# Power_Switch.net
KiCad netlist of a schematic drawn in Altium Designer
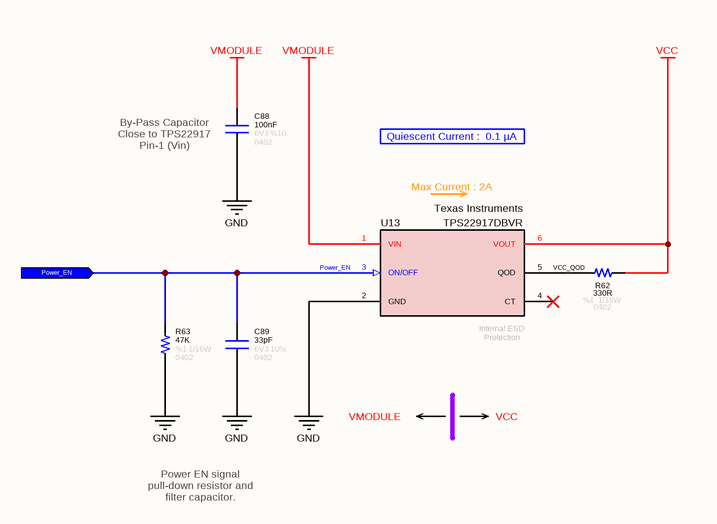
[diagram p0: Power Switch.SchDoc]

(export (version "E")
  (design (tool "Eeschema 10.0.6"))
  (components
    (comp (ref "C88")
      (value "100nF")
      (footprint "CAPACITOR_0402")
      (description "Capacitor - 100nF [0402-6V3] (Ceramic)")
      (fields
        (field (name "MANUFACTURER PART NUMBER") "04026D104KAT4A")
        (field (name "TOLERANCE") "%10")
        (field (name "VOLTAGE") "6V3")
        (field (name "CASE") "0402")
        (field (name "Comment") "Capacitor - 100nF [0402] (Ceramic)")
      )
      (libsource (lib "P101DA_Library") (part "Capacitor - 100nF [0402-6V3]"))
    )
    (comp (ref "C89")
      (value "33pF")
      (footprint "CAPACITOR_0402")
      (description "Capacitor - 33pF [0402] (Ceramic)")
      (fields
        (field (name "MANUFACTURER PART NUMBER") "C0402C330J9RACAUTO")
        (field (name "TOLERANCE") "10%")
        (field (name "CASE") "0402")
        (field (name "VOLTAGE") "6V3")
      )
      (libsource (lib "P101DA_Library") (part "Capacitor - 33pF [0402-6V3]"))
    )
    (comp (ref "R62")
      (value "330R")
      (footprint "RESISTOR_0402")
      (description "Thick Film Resistors - SMD 1/16 W 330 Ohm 1%")
      (fields
        (field (name "MANUFACTURER PART NUMBER") "CRCW0402330RFKED")
        (field (name "CASE") "0402")
        (field (name "TOLERANCE") "%1")
        (field (name "POWER") "1/16W")
        (field (name "Comment") "330R - 0402 - %1 - 1/16W")
      )
      (libsource (lib "P101DA_Library") (part "Resistor - 330R [0402]"))
    )
    (comp (ref "R63")
      (value "47K")
      (footprint "RESISTOR_0402")
      (description "Thick Film Resistors - SMD 1/16 W 47 KOhm 1%")
      (fields
        (field (name "MANUFACTURER PART NUMBER") "CRCW040247K0FKED")
        (field (name "TOLERANCE") "%1")
        (field (name "CASE") "0402")
        (field (name "POWER") "1/16W")
        (field (name "Comment") "47K - 0402 - %1 - 1/16W")
      )
      (libsource (lib "P101DA_Library") (part "Resistor - 47K [0402]"))
    )
    (comp (ref "U13")
      (value "Power Switch")
      (footprint "SOT-23-6")
      (description "Power Switch MosFet")
      (fields
        (field (name "MANUFACTURER PART NUMBER") "TPS22917DBVR")
        (field (name "MANUFACTURER NAME") "Texas Instruments")
      )
      (libsource (lib "P101DA_Library") (part "IC - TPS22917"))
    )
  )
  (nets
    (net (code "1") (name "/Power_EN") (class "Default")
      (node (ref "C89") (pin "2") (pinfunction "2_2") (pintype "passive"))
      (node (ref "R63") (pin "2") (pinfunction "2_2") (pintype "passive"))
      (node (ref "U13") (pin "3") (pinfunction "ON/OFF_3") (pintype "input"))
    )
    (net (code "2") (name "/VCC_QOD") (class "Default")
      (node (ref "R62") (pin "2") (pinfunction "2_2") (pintype "passive"))
      (node (ref "U13") (pin "5") (pinfunction "QOD_5") (pintype "power_in"))
    )
    (net (code "3") (name "GND") (class "Default")
      (node (ref "C88") (pin "1") (pinfunction "1_1") (pintype "passive"))
      (node (ref "C89") (pin "1") (pinfunction "1_1") (pintype "passive"))
      (node (ref "R63") (pin "1") (pinfunction "1_1") (pintype "passive"))
      (node (ref "U13") (pin "2") (pinfunction "GND_2") (pintype "power_in"))
    )
    (net (code "4") (name "VCC") (class "Default")
      (node (ref "R62") (pin "1") (pinfunction "1_1") (pintype "passive"))
      (node (ref "U13") (pin "6") (pinfunction "VOUT_6") (pintype "power_in"))
    )
    (net (code "5") (name "VMODULE") (class "Default")
      (node (ref "C88") (pin "2") (pinfunction "2_2") (pintype "passive"))
      (node (ref "U13") (pin "1") (pinfunction "VIN_1") (pintype "power_in"))
    )
    (net (code "6") (name "unconnected-(U13-CT-Pad4)") (class "Default")
      (node (ref "U13") (pin "4") (pinfunction "CT_4") (pintype "power_in+no_connect"))
    )
  )
)
